# space_invaders_v21_othermill.net
KiCad netlist of a schematic drawn in EAGLE
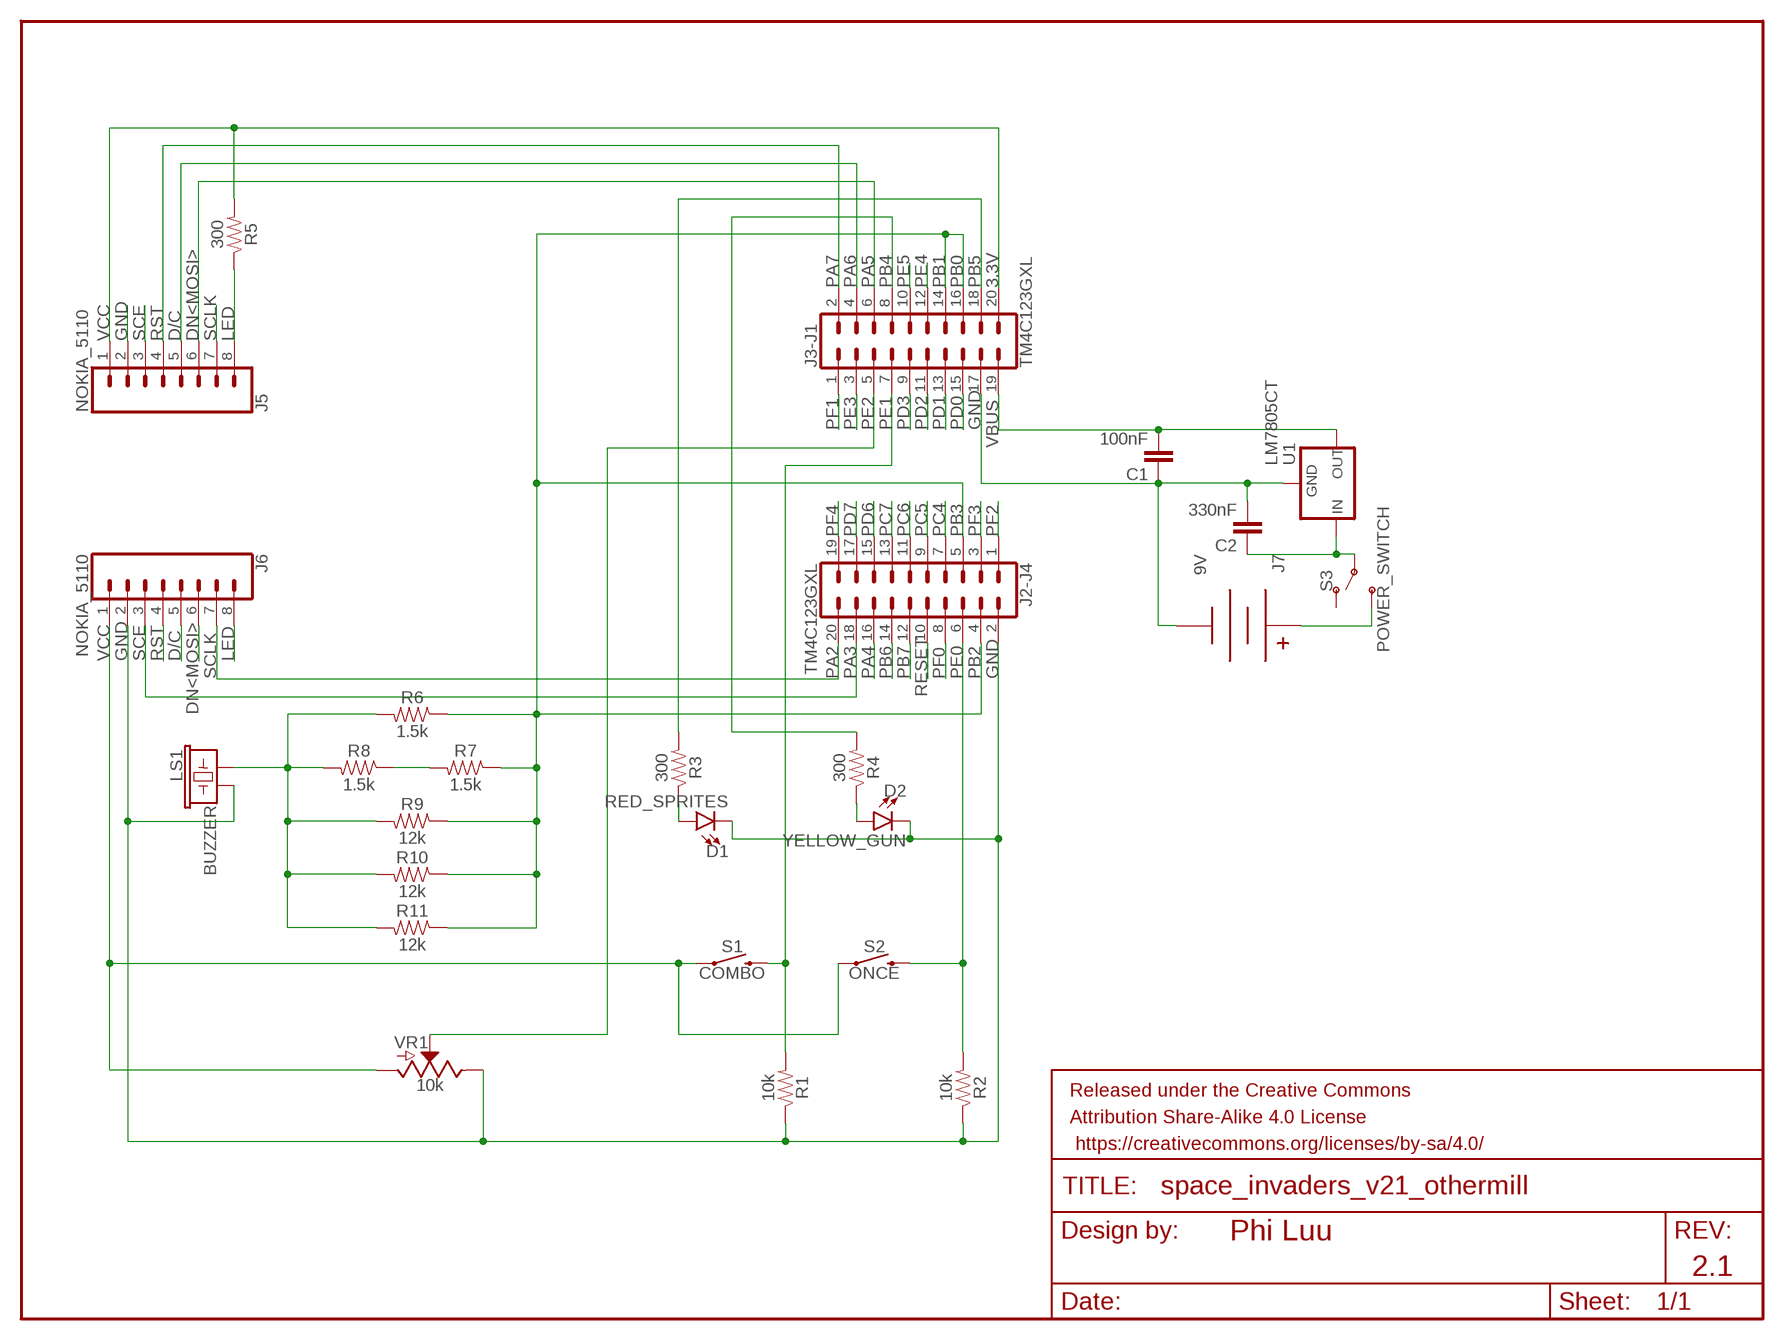
[diagram p0: schematic, sheet 1]

(export (version "E")
  (design (tool "Eeschema 10.0.6"))
  (components
    (comp (ref "C1")
      (value "100nF")
      (footprint "eagle-import:CAP-PTH-SMALL-KIT")
      (libsource (lib "eagle-import") (part "0.1UF-KIT-EZ-50V-20%"))
    )
    (comp (ref "C2")
      (value "330nF")
      (footprint "eagle-import:CAP-PTH-SMALL-KIT")
      (libsource (lib "eagle-import") (part "0.1UF-KIT-EZ-50V-20%"))
    )
    (comp (ref "D1")
      (value "RED_SPRITES")
      (footprint "eagle-import:LED_5MM")
      (libsource (lib "eagle-import") (part "LED5MM"))
    )
    (comp (ref "D2")
      (value "YELLOW_GUN")
      (footprint "eagle-import:LED_5MM")
      (libsource (lib "eagle-import") (part "LED5MM"))
    )
    (comp (ref "FRAME1")
      (value "FRAME-LETTER")
      (footprint "eagle-import:CREATIVE_COMMONS")
      (libsource (lib "eagle-import") (part "FRAME-LETTER"))
    )
    (comp (ref "J2-J4")
      (value "TM4C123GXL")
      (footprint "eagle-import:2X10")
      (libsource (lib "eagle-import") (part "CONN_10X2"))
    )
    (comp (ref "J3-J1")
      (value "TM4C123GXL")
      (footprint "eagle-import:2X10")
      (libsource (lib "eagle-import") (part "CONN_10X2"))
    )
    (comp (ref "J5")
      (value "NOKIA_5110")
      (footprint "eagle-import:1X08")
      (libsource (lib "eagle-import") (part "CONN_08{dblquote}"))
    )
    (comp (ref "J6")
      (value "NOKIA_5110")
      (footprint "eagle-import:1X08")
      (libsource (lib "eagle-import") (part "CONN_08{dblquote}"))
    )
    (comp (ref "J7")
      (value "9V")
      (footprint "eagle-import:BC9VPC")
      (libsource (lib "eagle-import") (part "BC9VPC"))
    )
    (comp (ref "LS1")
      (value "BUZZER")
      (footprint "eagle-import:BUZZER-12MM")
      (libsource (lib "eagle-import") (part "BUZZER-PTH"))
    )
    (comp (ref "R1")
      (value "10k")
      (footprint "eagle-import:AXIAL-0.3")
      (libsource (lib "eagle-import") (part "10KOHM-HORIZ-1/4W-5%"))
    )
    (comp (ref "R2")
      (value "10k")
      (footprint "eagle-import:AXIAL-0.3")
      (libsource (lib "eagle-import") (part "10KOHM-HORIZ-1/4W-5%"))
    )
    (comp (ref "R3")
      (value "300")
      (footprint "eagle-import:AXIAL-0.3")
      (libsource (lib "eagle-import") (part "1KOHM-HORIZ-1/4W-5%"))
    )
    (comp (ref "R4")
      (value "300")
      (footprint "eagle-import:AXIAL-0.3")
      (libsource (lib "eagle-import") (part "1KOHM-HORIZ-1/4W-5%"))
    )
    (comp (ref "R5")
      (value "300")
      (footprint "eagle-import:AXIAL-0.3")
      (libsource (lib "eagle-import") (part "1KOHM-HORIZ-1/4W-5%"))
    )
    (comp (ref "R6")
      (value "1.5k")
      (footprint "eagle-import:AXIAL-0.3")
      (libsource (lib "eagle-import") (part "1KOHM-HORIZ-1/4W-5%"))
    )
    (comp (ref "R7")
      (value "1.5k")
      (footprint "eagle-import:AXIAL-0.3")
      (libsource (lib "eagle-import") (part "1KOHM-HORIZ-1/4W-5%"))
    )
    (comp (ref "R8")
      (value "1.5k")
      (footprint "eagle-import:AXIAL-0.3")
      (libsource (lib "eagle-import") (part "1KOHM-HORIZ-1/4W-5%"))
    )
    (comp (ref "R9")
      (value "12k")
      (footprint "eagle-import:AXIAL-0.3")
      (libsource (lib "eagle-import") (part "1KOHM-HORIZ-1/4W-5%"))
    )
    (comp (ref "R10")
      (value "12k")
      (footprint "eagle-import:AXIAL-0.3")
      (libsource (lib "eagle-import") (part "1KOHM-HORIZ-1/4W-5%"))
    )
    (comp (ref "R11")
      (value "12k")
      (footprint "eagle-import:AXIAL-0.3")
      (libsource (lib "eagle-import") (part "1KOHM-HORIZ-1/4W-5%"))
    )
    (comp (ref "S1")
      (value "COMBO")
      (footprint "eagle-import:TACTILE_SWITCH_PTH_6.0MM")
      (libsource (lib "eagle-import") (part "MOMENTARY-SWITCH-SPST-PTH-6.0MM"))
    )
    (comp (ref "S2")
      (value "ONCE")
      (footprint "eagle-import:TACTILE_SWITCH_PTH_6.0MM")
      (libsource (lib "eagle-import") (part "MOMENTARY-SWITCH-SPST-PTH-6.0MM"))
    )
    (comp (ref "S3")
      (value "POWER_SWITCH")
      (footprint "eagle-import:SWITCH_SPDT_PTH_11.6X4.0MM")
      (libsource (lib "eagle-import") (part "SWITCH-SPDT-PTH-11.6X4.0MM"))
    )
    (comp (ref "U1")
      (value "LM7805CT")
      (footprint "eagle-import:TO220-IGO")
      (libsource (lib "eagle-import") (part "V_REG_78XXSINK"))
    )
    (comp (ref "VR1")
      (value "10k")
      (footprint "eagle-import:SLIDER-MEDIUM")
      (libsource (lib "eagle-import") (part "POTENTIOMETER_SLIDE-30MM-1/10W-20%"))
    )
  )
  (nets
    (net (code "1") (name "/3.3V") (class "Default")
      (node (ref "J3-J1") (pin "20") (pinfunction "20_20") (pintype "passive"))
      (node (ref "J5") (pin "1") (pinfunction "1_1") (pintype "passive"))
      (node (ref "J6") (pin "1") (pinfunction "1_1") (pintype "passive"))
      (node (ref "R5") (pin "P$2") (pinfunction "2_P$2") (pintype "passive"))
      (node (ref "S1") (pin "1") (pinfunction "1_1") (pintype "passive"))
      (node (ref "S2") (pin "1") (pinfunction "1_1") (pintype "passive"))
      (node (ref "VR1") (pin "BOTTOM") (pinfunction "A_BOTTOM") (pintype "passive"))
    )
    (net (code "2") (name "/GND") (class "Default")
      (node (ref "C1") (pin "1") (pinfunction "1_1") (pintype "passive"))
      (node (ref "C2") (pin "2") (pinfunction "2_2") (pintype "passive"))
      (node (ref "D1") (pin "K") (pinfunction "C_K") (pintype "passive"))
      (node (ref "D2") (pin "K") (pinfunction "C_K") (pintype "passive"))
      (node (ref "J2-J4") (pin "2") (pinfunction "2_2") (pintype "passive"))
      (node (ref "J3-J1") (pin "17") (pinfunction "17_17") (pintype "passive"))
      (node (ref "J5") (pin "2") (pinfunction "2_2") (pintype "passive"))
      (node (ref "J6") (pin "2") (pinfunction "2_2") (pintype "passive"))
      (node (ref "J7") (pin "V-") (pinfunction "V-_V-") (pintype "bidirectional"))
      (node (ref "LS1") (pin "-") (pinfunction "2_-") (pintype "passive"))
      (node (ref "R1") (pin "P$1") (pinfunction "1_P$1") (pintype "passive"))
      (node (ref "R2") (pin "P$1") (pinfunction "1_P$1") (pintype "passive"))
      (node (ref "U1") (pin "GND") (pinfunction "GND_GND") (pintype "input"))
      (node (ref "VR1") (pin "TOP") (pinfunction "E_TOP") (pintype "passive"))
    )
    (net (code "3") (name "/LED") (class "Default")
      (node (ref "J5") (pin "8") (pinfunction "8_8") (pintype "passive"))
      (node (ref "J6") (pin "8") (pinfunction "8_8") (pintype "passive"))
      (node (ref "R5") (pin "P$1") (pinfunction "1_P$1") (pintype "passive"))
    )
    (net (code "4") (name "/PA2") (class "Default")
      (node (ref "J2-J4") (pin "20") (pinfunction "20_20") (pintype "passive"))
      (node (ref "J5") (pin "7") (pinfunction "7_7") (pintype "passive"))
      (node (ref "J6") (pin "7") (pinfunction "7_7") (pintype "passive"))
    )
    (net (code "5") (name "/PA3") (class "Default")
      (node (ref "J2-J4") (pin "18") (pinfunction "18_18") (pintype "passive"))
      (node (ref "J5") (pin "3") (pinfunction "3_3") (pintype "passive"))
      (node (ref "J6") (pin "3") (pinfunction "3_3") (pintype "passive"))
    )
    (net (code "6") (name "/PA4") (class "Default")
      (node (ref "J2-J4") (pin "16") (pinfunction "16_16") (pintype "passive"))
    )
    (net (code "7") (name "/PA5") (class "Default")
      (node (ref "J3-J1") (pin "6") (pinfunction "6_6") (pintype "passive"))
      (node (ref "J5") (pin "6") (pinfunction "6_6") (pintype "passive"))
      (node (ref "J6") (pin "6") (pinfunction "6_6") (pintype "passive"))
    )
    (net (code "8") (name "/PA6") (class "Default")
      (node (ref "J3-J1") (pin "4") (pinfunction "4_4") (pintype "passive"))
      (node (ref "J5") (pin "5") (pinfunction "5_5") (pintype "passive"))
      (node (ref "J6") (pin "5") (pinfunction "5_5") (pintype "passive"))
    )
    (net (code "9") (name "/PA7") (class "Default")
      (node (ref "J3-J1") (pin "2") (pinfunction "2_2") (pintype "passive"))
      (node (ref "J5") (pin "4") (pinfunction "4_4") (pintype "passive"))
      (node (ref "J6") (pin "4") (pinfunction "4_4") (pintype "passive"))
    )
    (net (code "10") (name "/PB4") (class "Default")
      (node (ref "J3-J1") (pin "8") (pinfunction "8_8") (pintype "passive"))
      (node (ref "R4") (pin "P$2") (pinfunction "2_P$2") (pintype "passive"))
    )
    (net (code "11") (name "/PB5") (class "Default")
      (node (ref "J3-J1") (pin "18") (pinfunction "18_18") (pintype "passive"))
      (node (ref "R3") (pin "P$2") (pinfunction "2_P$2") (pintype "passive"))
    )
    (net (code "12") (name "/PB6") (class "Default")
      (node (ref "J2-J4") (pin "14") (pinfunction "14_14") (pintype "passive"))
    )
    (net (code "13") (name "/PB7") (class "Default")
      (node (ref "J2-J4") (pin "12") (pinfunction "12_12") (pintype "passive"))
    )
    (net (code "14") (name "/PC4") (class "Default")
      (node (ref "J2-J4") (pin "7") (pinfunction "7_7") (pintype "passive"))
    )
    (net (code "15") (name "/PC5") (class "Default")
      (node (ref "J2-J4") (pin "9") (pinfunction "9_9") (pintype "passive"))
    )
    (net (code "16") (name "/PC6") (class "Default")
      (node (ref "J2-J4") (pin "11") (pinfunction "11_11") (pintype "passive"))
    )
    (net (code "17") (name "/PC7") (class "Default")
      (node (ref "J2-J4") (pin "13") (pinfunction "13_13") (pintype "passive"))
    )
    (net (code "18") (name "/PD0") (class "Default")
      (node (ref "J3-J1") (pin "15") (pinfunction "15_15") (pintype "passive"))
    )
    (net (code "19") (name "/PD1") (class "Default")
      (node (ref "J3-J1") (pin "13") (pinfunction "13_13") (pintype "passive"))
    )
    (net (code "20") (name "/PD2") (class "Default")
      (node (ref "J3-J1") (pin "11") (pinfunction "11_11") (pintype "passive"))
    )
    (net (code "21") (name "/PD3") (class "Default")
      (node (ref "J3-J1") (pin "9") (pinfunction "9_9") (pintype "passive"))
    )
    (net (code "22") (name "/PD6") (class "Default")
      (node (ref "J2-J4") (pin "15") (pinfunction "15_15") (pintype "passive"))
    )
    (net (code "23") (name "/PD7") (class "Default")
      (node (ref "J2-J4") (pin "17") (pinfunction "17_17") (pintype "passive"))
    )
    (net (code "24") (name "/PE0") (class "Default")
      (node (ref "J2-J4") (pin "6") (pinfunction "6_6") (pintype "passive"))
      (node (ref "R2") (pin "P$2") (pinfunction "2_P$2") (pintype "passive"))
      (node (ref "S2") (pin "3") (pinfunction "2_3") (pintype "passive"))
    )
    (net (code "25") (name "/PE1") (class "Default")
      (node (ref "J3-J1") (pin "7") (pinfunction "7_7") (pintype "passive"))
      (node (ref "R1") (pin "P$2") (pinfunction "2_P$2") (pintype "passive"))
      (node (ref "S1") (pin "3") (pinfunction "2_3") (pintype "passive"))
    )
    (net (code "26") (name "/PE2") (class "Default")
      (node (ref "J3-J1") (pin "5") (pinfunction "5_5") (pintype "passive"))
      (node (ref "VR1") (pin "WIPER") (pinfunction "S_WIPER") (pintype "passive"))
    )
    (net (code "27") (name "/PE3") (class "Default")
      (node (ref "J3-J1") (pin "3") (pinfunction "3_3") (pintype "passive"))
    )
    (net (code "28") (name "/PE4") (class "Default")
      (node (ref "J3-J1") (pin "12") (pinfunction "12_12") (pintype "passive"))
    )
    (net (code "29") (name "/PE5") (class "Default")
      (node (ref "J3-J1") (pin "10") (pinfunction "10_10") (pintype "passive"))
    )
    (net (code "30") (name "/PF0") (class "Default")
      (node (ref "J2-J4") (pin "8") (pinfunction "8_8") (pintype "passive"))
    )
    (net (code "31") (name "/PF1") (class "Default")
      (node (ref "J3-J1") (pin "1") (pinfunction "1_1") (pintype "passive"))
    )
    (net (code "32") (name "/PF2") (class "Default")
      (node (ref "J2-J4") (pin "1") (pinfunction "1_1") (pintype "passive"))
    )
    (net (code "33") (name "/PF3") (class "Default")
      (node (ref "J2-J4") (pin "3") (pinfunction "3_3") (pintype "passive"))
    )
    (net (code "34") (name "/PF4") (class "Default")
      (node (ref "J2-J4") (pin "19") (pinfunction "19_19") (pintype "passive"))
    )
    (net (code "35") (name "/RESET") (class "Default")
      (node (ref "J2-J4") (pin "10") (pinfunction "10_10") (pintype "passive"))
    )
    (net (code "36") (name "/VBUS") (class "Default")
      (node (ref "C1") (pin "2") (pinfunction "2_2") (pintype "passive"))
      (node (ref "J3-J1") (pin "19") (pinfunction "19_19") (pintype "passive"))
      (node (ref "U1") (pin "OUT") (pinfunction "OUT_OUT") (pintype "passive"))
    )
    (net (code "37") (name "Net-(LS1-1)") (class "Default")
      (node (ref "LS1") (pin "+") (pinfunction "1_+") (pintype "passive"))
      (node (ref "R10") (pin "P$2") (pinfunction "2_P$2") (pintype "passive"))
      (node (ref "R11") (pin "P$2") (pinfunction "2_P$2") (pintype "passive"))
      (node (ref "R6") (pin "P$2") (pinfunction "2_P$2") (pintype "passive"))
      (node (ref "R8") (pin "P$2") (pinfunction "2_P$2") (pintype "passive"))
      (node (ref "R9") (pin "P$2") (pinfunction "2_P$2") (pintype "passive"))
    )
    (net (code "38") (name "Net-(R3-1)") (class "Default")
      (node (ref "D1") (pin "A") (pinfunction "A_A") (pintype "passive"))
      (node (ref "R3") (pin "P$1") (pinfunction "1_P$1") (pintype "passive"))
    )
    (net (code "39") (name "Net-(R4-1)") (class "Default")
      (node (ref "D2") (pin "A") (pinfunction "A_A") (pintype "passive"))
      (node (ref "R4") (pin "P$1") (pinfunction "1_P$1") (pintype "passive"))
    )
    (net (code "40") (name "Net-(R7-2)") (class "Default")
      (node (ref "R7") (pin "P$2") (pinfunction "2_P$2") (pintype "passive"))
      (node (ref "R8") (pin "P$1") (pinfunction "1_P$1") (pintype "passive"))
    )
    (net (code "41") (name "Net-(R10-1)") (class "Default")
      (node (ref "J2-J4") (pin "4") (pinfunction "4_4") (pintype "passive"))
      (node (ref "J2-J4") (pin "5") (pinfunction "5_5") (pintype "passive"))
      (node (ref "J3-J1") (pin "14") (pinfunction "14_14") (pintype "passive"))
      (node (ref "J3-J1") (pin "16") (pinfunction "16_16") (pintype "passive"))
      (node (ref "R10") (pin "P$1") (pinfunction "1_P$1") (pintype "passive"))
      (node (ref "R11") (pin "P$1") (pinfunction "1_P$1") (pintype "passive"))
      (node (ref "R6") (pin "P$1") (pinfunction "1_P$1") (pintype "passive"))
      (node (ref "R7") (pin "P$1") (pinfunction "1_P$1") (pintype "passive"))
      (node (ref "R9") (pin "P$1") (pinfunction "1_P$1") (pintype "passive"))
    )
    (net (code "42") (name "Net-(S3-P)") (class "Default")
      (node (ref "C2") (pin "1") (pinfunction "1_1") (pintype "passive"))
      (node (ref "S3") (pin "2") (pinfunction "P_2") (pintype "passive"))
      (node (ref "U1") (pin "IN") (pinfunction "IN_IN") (pintype "input"))
    )
    (net (code "43") (name "Net-(S3-S)") (class "Default")
      (node (ref "J7") (pin "V+") (pinfunction "V+_V+") (pintype "bidirectional"))
      (node (ref "S3") (pin "3") (pinfunction "S_3") (pintype "passive"))
    )
    (net (code "44") (name "unconnected-(S3-O-Pad1)") (class "Default")
      (node (ref "S3") (pin "1") (pinfunction "O_1") (pintype "passive"))
    )
  )
)
